# SparkFun_openScale.net
KiCad netlist of a schematic drawn in EAGLE
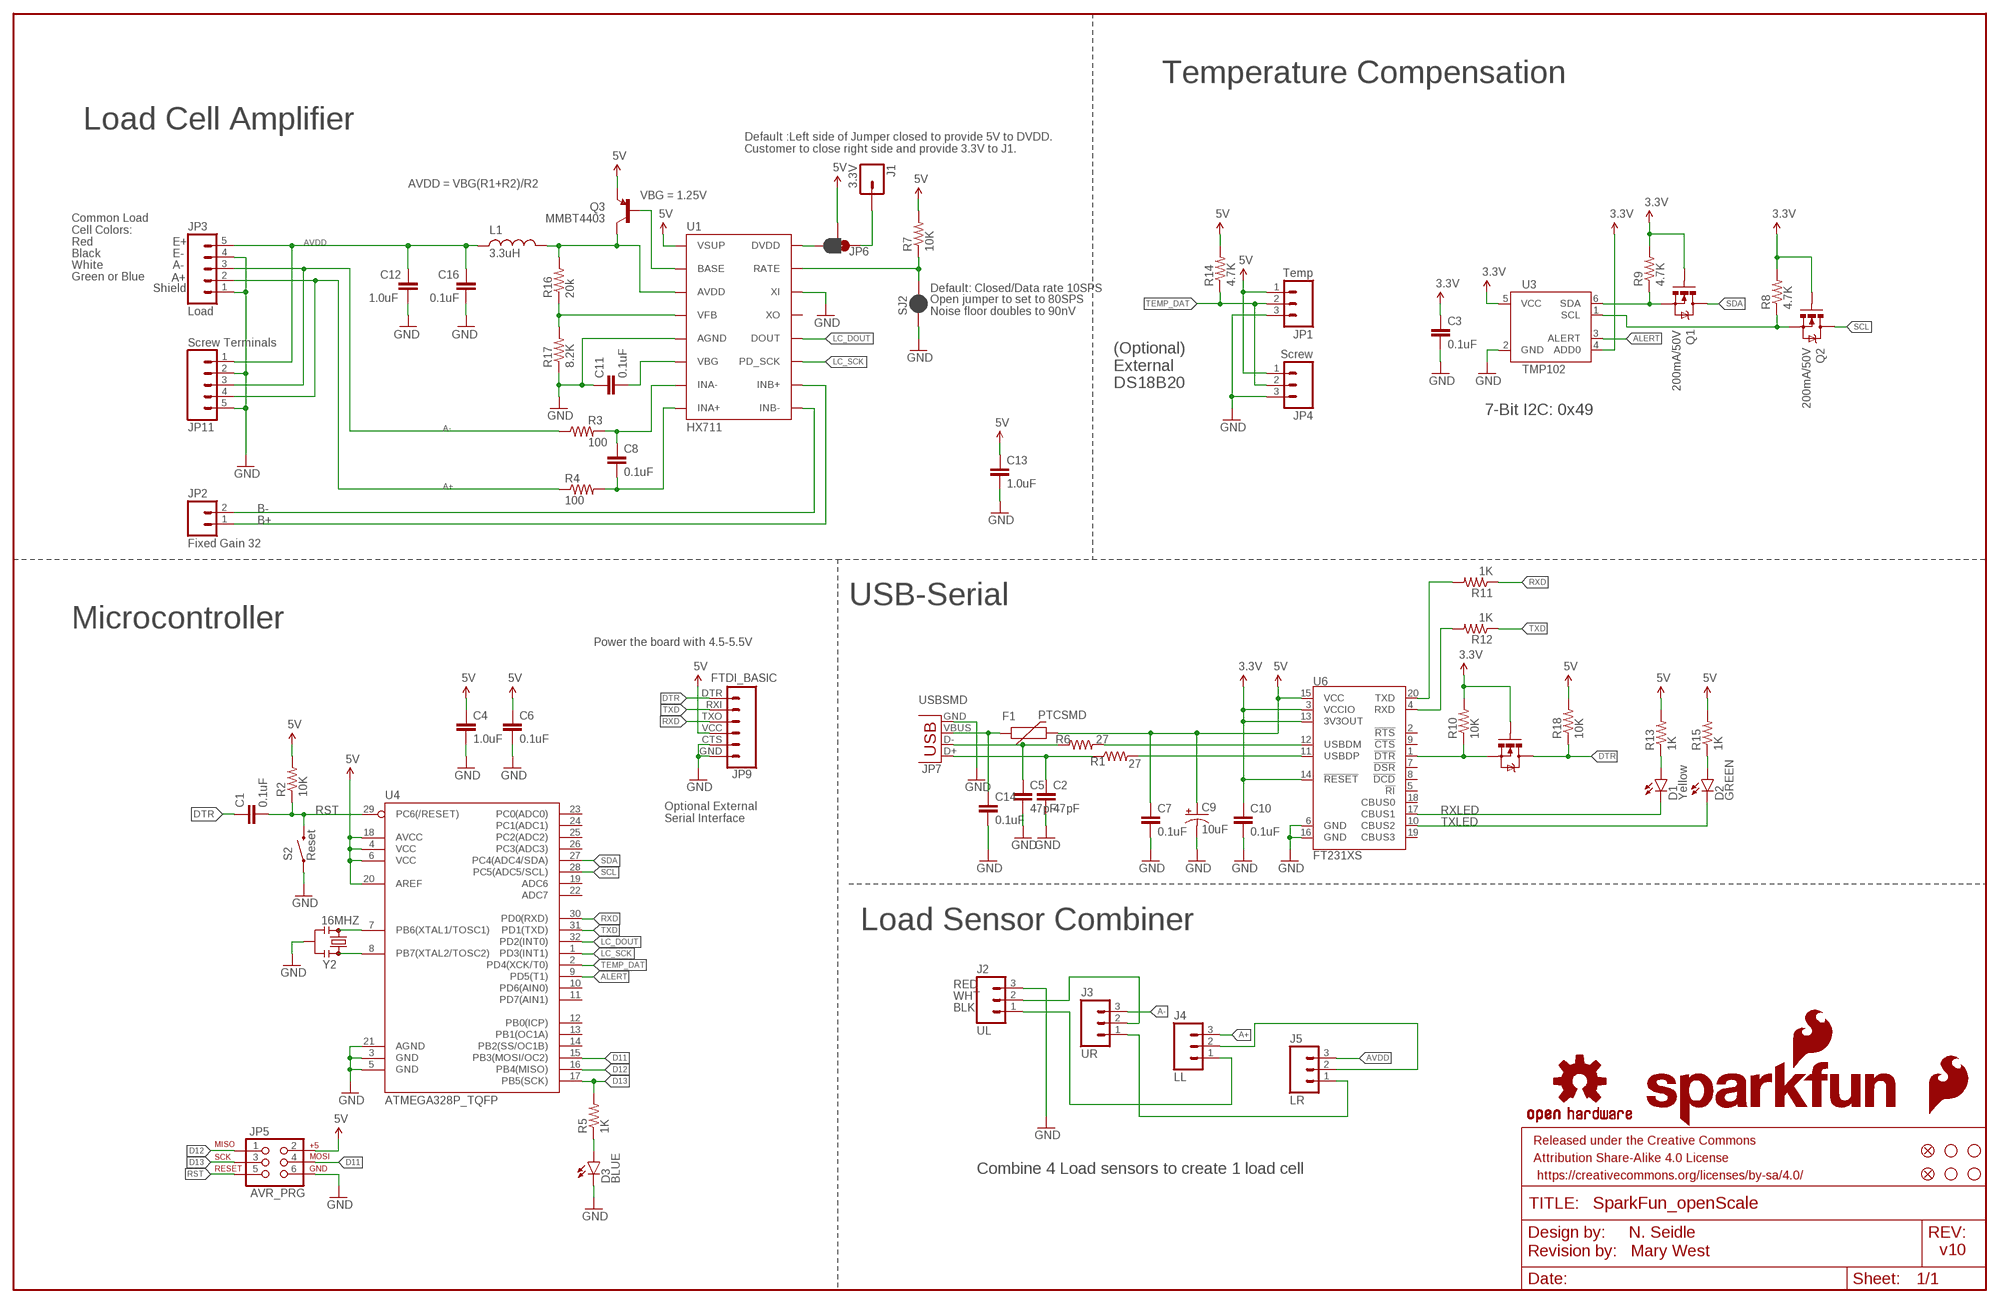
[diagram p0: schematic, sheet 1]

(export (version "E")
  (design (tool "Eeschema 10.0.6"))
  (components
    (comp (ref "C1")
      (value "0.1uF")
      (footprint "eagle-import:0603-CAP")
      (libsource (lib "eagle-import") (part "0.1UF-25V(+80/-20%)(0603)"))
    )
    (comp (ref "C2")
      (value "47pF")
      (footprint "eagle-import:0603-CAP")
      (libsource (lib "eagle-import") (part "47PF-50V-5%(0603)"))
    )
    (comp (ref "C3")
      (value "0.1uF")
      (footprint "eagle-import:0603-CAP")
      (libsource (lib "eagle-import") (part "0.1UF-25V(+80/-20%)(0603)"))
    )
    (comp (ref "C4")
      (value "1.0uF")
      (footprint "eagle-import:0603-CAP")
      (libsource (lib "eagle-import") (part "1.0UF-16V-10%(0603)"))
    )
    (comp (ref "C5")
      (value "47pF")
      (footprint "eagle-import:0603-CAP")
      (libsource (lib "eagle-import") (part "47PF-50V-5%(0603)"))
    )
    (comp (ref "C6")
      (value "0.1uF")
      (footprint "eagle-import:0603-CAP")
      (libsource (lib "eagle-import") (part "0.1UF-25V(+80/-20%)(0603)"))
    )
    (comp (ref "C7")
      (value "0.1uF")
      (footprint "eagle-import:0603-CAP")
      (libsource (lib "eagle-import") (part "0.1UF-25V(+80/-20%)(0603)"))
    )
    (comp (ref "C8")
      (value "0.1uF")
      (footprint "eagle-import:0603-CAP")
      (libsource (lib "eagle-import") (part "0.1UF-25V(+80/-20%)(0603)"))
    )
    (comp (ref "C9")
      (value "10uF")
      (footprint "eagle-import:EIA3216")
      (libsource (lib "eagle-import") (part "10UF-16V-10%(TANT)"))
    )
    (comp (ref "C10")
      (value "0.1uF")
      (footprint "eagle-import:0603-CAP")
      (libsource (lib "eagle-import") (part "0.1UF-25V(+80/-20%)(0603)"))
    )
    (comp (ref "C11")
      (value "0.1uF")
      (footprint "eagle-import:0603-CAP")
      (libsource (lib "eagle-import") (part "0.1UF-25V(+80/-20%)(0603)"))
    )
    (comp (ref "C12")
      (value "1.0uF")
      (footprint "eagle-import:0603-CAP")
      (libsource (lib "eagle-import") (part "1.0UF-16V-10%(0603)"))
    )
    (comp (ref "C13")
      (value "1.0uF")
      (footprint "eagle-import:0603-CAP")
      (libsource (lib "eagle-import") (part "1.0UF-16V-10%(0603)"))
    )
    (comp (ref "C14")
      (value "0.1uF")
      (footprint "eagle-import:0603-CAP")
      (libsource (lib "eagle-import") (part "0.1UF-25V(+80/-20%)(0603)"))
    )
    (comp (ref "C16")
      (value "0.1uF")
      (footprint "eagle-import:0603-CAP")
      (libsource (lib "eagle-import") (part "0.1UF-25V(+80/-20%)(0603)"))
    )
    (comp (ref "D1")
      (value "Yellow")
      (footprint "eagle-import:LED-1206")
      (libsource (lib "eagle-import") (part "LED-YELLOWLILYPAD"))
    )
    (comp (ref "D2")
      (value "GREEN")
      (footprint "eagle-import:LED-1206")
      (libsource (lib "eagle-import") (part "LED-GREEN1206"))
    )
    (comp (ref "D3")
      (value "BLUE")
      (footprint "eagle-import:LED-1206")
      (libsource (lib "eagle-import") (part "LED-BLUE1206"))
    )
    (comp (ref "F1")
      (value "PTCSMD")
      (footprint "eagle-import:PTC-1206")
      (libsource (lib "eagle-import") (part "PTCSMD"))
    )
    (comp (ref "FID1")
      (value "FIDUCIALUFIDUCIAL")
      (footprint "eagle-import:MICRO-FIDUCIAL")
      (libsource (lib "eagle-import") (part "FIDUCIALUFIDUCIAL"))
    )
    (comp (ref "FID2")
      (value "FIDUCIALUFIDUCIAL")
      (footprint "eagle-import:MICRO-FIDUCIAL")
      (libsource (lib "eagle-import") (part "FIDUCIALUFIDUCIAL"))
    )
    (comp (ref "FRAME1")
      (value "FRAME-LEDGER")
      (footprint "eagle-import:CREATIVE_COMMONS")
      (fields (field (name "DESIGNER") "N. Seidle") (field (name "VERSION") "v02"))
      (libsource (lib "eagle-import") (part "FRAME-LEDGER"))
    )
    (comp (ref "J1")
      (value "3.3V")
      (footprint "eagle-import:1X01")
      (libsource (lib "eagle-import") (part "M01PTH"))
    )
    (comp (ref "J2")
      (value "UL")
      (footprint "eagle-import:1X03")
      (libsource (lib "eagle-import") (part "M03PTH"))
    )
    (comp (ref "J3")
      (value "UR")
      (footprint "eagle-import:1X03")
      (libsource (lib "eagle-import") (part "M03PTH"))
    )
    (comp (ref "J4")
      (value "LL")
      (footprint "eagle-import:1X03")
      (libsource (lib "eagle-import") (part "M03PTH"))
    )
    (comp (ref "J5")
      (value "LR")
      (footprint "eagle-import:1X03")
      (libsource (lib "eagle-import") (part "M03PTH"))
    )
    (comp (ref "JP1")
      (value "Temp")
      (footprint "eagle-import:1X03_NO_SILK")
      (libsource (lib "eagle-import") (part "M031X03_NO_SILK"))
    )
    (comp (ref "JP2")
      (value "Fixed Gain 32")
      (footprint "eagle-import:1X02")
      (libsource (lib "eagle-import") (part "M02PTH"))
    )
    (comp (ref "JP3")
      (value "Load")
      (footprint "eagle-import:1X05_NO_SILK")
      (libsource (lib "eagle-import") (part "M05NO_SILK"))
    )
    (comp (ref "JP4")
      (value "Screw")
      (footprint "eagle-import:SCREWTERMINAL-3.5MM-3_LOCK.007S")
      (libsource (lib "eagle-import") (part "M03SCREW_LOCK"))
    )
    (comp (ref "JP5")
      (value "AVR_PRG")
      (footprint "eagle-import:2X3")
      (libsource (lib "eagle-import") (part "AVR_SPI_PRG_6PTH"))
    )
    (comp (ref "JP6")
      (value "JUMPER-PAD-3-2OF3_NC_BY_PASTE")
      (footprint "eagle-import:PAD-JUMPER-3-2OF3_NC_BY_PASTE_YES_SILK_FULL_BOX")
      (libsource (lib "eagle-import") (part "JUMPER-PAD-3-2OF3_NC_BY_PASTE"))
    )
    (comp (ref "JP7")
      (value "USBSMD")
      (footprint "eagle-import:USB-MINIB")
      (libsource (lib "eagle-import") (part "USBSMD"))
    )
    (comp (ref "JP9")
      (value "FTDI_BASIC")
      (footprint "eagle-import:FTDI_BASIC")
      (libsource (lib "eagle-import") (part "FTDI_BASICPTH"))
    )
    (comp (ref "JP11")
      (value "Screw Terminals")
      (footprint "eagle-import:SCREWTERMINAL-3.5MM-5")
      (libsource (lib "eagle-import") (part "M05SCREW"))
    )
    (comp (ref "L1")
      (value "3.3uH")
      (footprint "eagle-import:0805")
      (libsource (lib "eagle-import") (part "INDUCTOR0805-IND"))
    )
    (comp (ref "LOGO2")
      (value "OSHW-LOGOS")
      (footprint "eagle-import:OSHW-LOGO-S")
      (libsource (lib "eagle-import") (part "OSHW-LOGOS"))
    )
    (comp (ref "LOGO3")
      (value "SFE_LOGO_FLAME.1_INCH")
      (footprint "eagle-import:SFE_LOGO_FLAME_.1")
      (libsource (lib "eagle-import") (part "SFE_LOGO_FLAME.1_INCH"))
    )
    (comp (ref "LOGO4")
      (value "SFE_LOGO_NAME_FLAME.1_INCH")
      (footprint "eagle-import:SFE_LOGO_NAME_FLAME_.1")
      (libsource (lib "eagle-import") (part "SFE_LOGO_NAME_FLAME.1_INCH"))
    )
    (comp (ref "Q1")
      (value "200mA/50V")
      (footprint "eagle-import:SOT23-3")
      (libsource (lib "eagle-import") (part "MOSFET-NCHANNELBSS138"))
    )
    (comp (ref "Q2")
      (value "200mA/50V")
      (footprint "eagle-import:SOT23-3")
      (libsource (lib "eagle-import") (part "MOSFET-NCHANNELBSS138"))
    )
    (comp (ref "Q3")
      (value "MMBT4403")
      (footprint "eagle-import:SOT23-3")
      (libsource (lib "eagle-import") (part "TRANSISTOR_PNPMMBT4403"))
    )
    (comp (ref "Q4")
      (value "MOSFET-NCHANNEL2N7002PW")
      (footprint "eagle-import:SOT323")
      (libsource (lib "eagle-import") (part "MOSFET-NCHANNEL2N7002PW"))
    )
    (comp (ref "R1")
      (value "27")
      (footprint "eagle-import:0603")
      (libsource (lib "eagle-import") (part "27OHM1/10W1%(0603)"))
    )
    (comp (ref "R2")
      (value "10K")
      (footprint "eagle-import:0603-RES")
      (libsource (lib "eagle-import") (part "10KOHM-1/10W-1%(0603)0603"))
    )
    (comp (ref "R3")
      (value "100")
      (footprint "eagle-import:0603-RES")
      (libsource (lib "eagle-import") (part "100OHM-1/10W-1%(0603)"))
    )
    (comp (ref "R4")
      (value "100")
      (footprint "eagle-import:0603-RES")
      (libsource (lib "eagle-import") (part "100OHM-1/10W-1%(0603)"))
    )
    (comp (ref "R5")
      (value "1K")
      (footprint "eagle-import:0603-RES")
      (libsource (lib "eagle-import") (part "1KOHM-1/10W-1%(0603)"))
    )
    (comp (ref "R6")
      (value "27")
      (footprint "eagle-import:0603")
      (libsource (lib "eagle-import") (part "27OHM1/10W1%(0603)"))
    )
    (comp (ref "R7")
      (value "10K")
      (footprint "eagle-import:0603-RES")
      (libsource (lib "eagle-import") (part "10KOHM-1/10W-1%(0603)0603"))
    )
    (comp (ref "R8")
      (value "4.7K")
      (footprint "eagle-import:0603-RES")
      (libsource (lib "eagle-import") (part "4.7KOHM-1/10W-1%(0603)"))
    )
    (comp (ref "R9")
      (value "4.7K")
      (footprint "eagle-import:0603-RES")
      (libsource (lib "eagle-import") (part "4.7KOHM-1/10W-1%(0603)"))
    )
    (comp (ref "R10")
      (value "10K")
      (footprint "eagle-import:0603-RES")
      (libsource (lib "eagle-import") (part "10KOHM-1/10W-1%(0603)0603"))
    )
    (comp (ref "R11")
      (value "1K")
      (footprint "eagle-import:0603-RES")
      (libsource (lib "eagle-import") (part "1KOHM-1/10W-1%(0603)"))
    )
    (comp (ref "R12")
      (value "1K")
      (footprint "eagle-import:0603-RES")
      (libsource (lib "eagle-import") (part "1KOHM-1/10W-1%(0603)"))
    )
    (comp (ref "R13")
      (value "1K")
      (footprint "eagle-import:0603-RES")
      (libsource (lib "eagle-import") (part "1KOHM-1/10W-1%(0603)"))
    )
    (comp (ref "R14")
      (value "4.7K")
      (footprint "eagle-import:0603-RES")
      (libsource (lib "eagle-import") (part "4.7KOHM-1/10W-1%(0603)"))
    )
    (comp (ref "R15")
      (value "1K")
      (footprint "eagle-import:0603-RES")
      (libsource (lib "eagle-import") (part "1KOHM-1/10W-1%(0603)"))
    )
    (comp (ref "R16")
      (value "20k")
      (footprint "eagle-import:0603-RES")
      (libsource (lib "eagle-import") (part "20KOHM1/10W1%(0603)"))
    )
    (comp (ref "R17")
      (value "8.2K")
      (footprint "eagle-import:0603-RES")
      (libsource (lib "eagle-import") (part "8.2KOHM-1/10W-5%(0603)"))
    )
    (comp (ref "R18")
      (value "10K")
      (footprint "eagle-import:0603-RES")
      (libsource (lib "eagle-import") (part "10KOHM-1/10W-1%(0603)0603"))
    )
    (comp (ref "S2")
      (value "Reset")
      (footprint "eagle-import:TACTILE-SWITCH-SMD")
      (libsource (lib "eagle-import") (part "SWITCH-MOMENTARY-2SMD"))
    )
    (comp (ref "SJ2")
      (value "JUMPER-PAD-2-NC_BY_PASTE")
      (footprint "eagle-import:PAD-JUMPER-2-NC_BY_PASTE_YES_SILK")
      (libsource (lib "eagle-import") (part "JUMPER-PAD-2-NC_BY_PASTE"))
    )
    (comp (ref "STANDOFF1")
      (value "STAND-OFF")
      (footprint "eagle-import:STAND-OFF")
      (libsource (lib "eagle-import") (part "STAND-OFF"))
    )
    (comp (ref "STANDOFF2")
      (value "STAND-OFF")
      (footprint "eagle-import:STAND-OFF")
      (libsource (lib "eagle-import") (part "STAND-OFF"))
    )
    (comp (ref "STANDOFF3")
      (value "STAND-OFF")
      (footprint "eagle-import:STAND-OFF")
      (libsource (lib "eagle-import") (part "STAND-OFF"))
    )
    (comp (ref "STANDOFF4")
      (value "STAND-OFF")
      (footprint "eagle-import:STAND-OFF")
      (libsource (lib "eagle-import") (part "STAND-OFF"))
    )
    (comp (ref "U1")
      (value "HX711")
      (footprint "eagle-import:SO16")
      (libsource (lib "eagle-import") (part "HX711HX711"))
    )
    (comp (ref "U3")
      (value "TMP102")
      (footprint "eagle-import:SOT563")
      (libsource (lib "eagle-import") (part "TMP102"))
    )
    (comp (ref "U4")
      (value "ATMEGA328P_TQFP")
      (footprint "eagle-import:TQFP32-08")
      (libsource (lib "eagle-import") (part "ATMEGA328P_TQFP"))
    )
    (comp (ref "U6")
      (value "FT231XS")
      (footprint "eagle-import:SSOP20_L")
      (libsource (lib "eagle-import") (part "FT231XS"))
    )
    (comp (ref "Y2")
      (value "16MHZ")
      (footprint "eagle-import:RESONATOR-SMD")
      (libsource (lib "eagle-import") (part "RESONATOR16MHZ"))
    )
  )
  (nets
    (net (code "1") (name "/B+") (class "Default")
      (node (ref "JP2") (pin "1") (pinfunction "1_1") (pintype "passive"))
      (node (ref "U1") (pin "10") (pinfunction "INB+_10") (pintype "bidirectional"))
    )
    (net (code "2") (name "/B-") (class "Default")
      (node (ref "JP2") (pin "2") (pinfunction "2_2") (pintype "passive"))
      (node (ref "U1") (pin "9") (pinfunction "INB-_9") (pintype "bidirectional"))
    )
    (net (code "3") (name "/RXLED") (class "Default")
      (node (ref "D1") (pin "C") (pinfunction "C_C") (pintype "passive"))
      (node (ref "U6") (pin "17") (pinfunction "CBUS1_17") (pintype "bidirectional"))
    )
    (net (code "4") (name "/TXLED") (class "Default")
      (node (ref "D2") (pin "C") (pinfunction "C_C") (pintype "passive"))
      (node (ref "U6") (pin "10") (pinfunction "CBUS2_10") (pintype "bidirectional"))
    )
    (net (code "5") (name "3.3V") (class "Default")
      (node (ref "C10") (pin "1") (pinfunction "1_1") (pintype "passive"))
      (node (ref "C3") (pin "1") (pinfunction "1_1") (pintype "passive"))
      (node (ref "Q1") (pin "1") (pinfunction "G_1") (pintype "passive"))
      (node (ref "Q2") (pin "1") (pinfunction "G_1") (pintype "passive"))
      (node (ref "Q4") (pin "1") (pinfunction "G_1") (pintype "passive"))
      (node (ref "R10") (pin "2") (pinfunction "2_2") (pintype "passive"))
      (node (ref "R8") (pin "2") (pinfunction "2_2") (pintype "passive"))
      (node (ref "R9") (pin "2") (pinfunction "2_2") (pintype "passive"))
      (node (ref "U3") (pin "4") (pinfunction "ADD0_4") (pintype "bidirectional"))
      (node (ref "U3") (pin "5") (pinfunction "VCC_5") (pintype "bidirectional"))
      (node (ref "U6") (pin "13") (pinfunction "3V3OUT_13") (pintype "bidirectional"))
      (node (ref "U6") (pin "14") (pinfunction "~{RESET}_14") (pintype "bidirectional"))
      (node (ref "U6") (pin "3") (pinfunction "VCCIO_3") (pintype "bidirectional"))
    )
    (net (code "6") (name "5V") (class "Default")
      (node (ref "C13") (pin "1") (pinfunction "1_1") (pintype "passive"))
      (node (ref "C4") (pin "1") (pinfunction "1_1") (pintype "passive"))
      (node (ref "C6") (pin "1") (pinfunction "1_1") (pintype "passive"))
      (node (ref "C7") (pin "1") (pinfunction "1_1") (pintype "passive"))
      (node (ref "C9") (pin "A") (pinfunction "+_A") (pintype "passive"))
      (node (ref "F1") (pin "2") (pinfunction "2_2") (pintype "bidirectional"))
      (node (ref "JP1") (pin "1") (pinfunction "1_1") (pintype "passive"))
      (node (ref "JP4") (pin "1") (pinfunction "1_1") (pintype "passive"))
      (node (ref "JP5") (pin "2") (pinfunction "2_2") (pintype "passive"))
      (node (ref "JP6") (pin "2") (pinfunction "2_2") (pintype "passive"))
      (node (ref "JP9") (pin "VCC") (pinfunction "4_VCC") (pintype "passive"))
      (node (ref "Q3") (pin "2") (pinfunction "E_2") (pintype "passive"))
      (node (ref "R13") (pin "2") (pinfunction "2_2") (pintype "passive"))
      (node (ref "R14") (pin "2") (pinfunction "2_2") (pintype "passive"))
      (node (ref "R15") (pin "2") (pinfunction "2_2") (pintype "passive"))
      (node (ref "R18") (pin "2") (pinfunction "2_2") (pintype "passive"))
      (node (ref "R2") (pin "2") (pinfunction "2_2") (pintype "passive"))
      (node (ref "R7") (pin "2") (pinfunction "2_2") (pintype "passive"))
      (node (ref "U1") (pin "1") (pinfunction "VSUP_1") (pintype "bidirectional"))
      (node (ref "U4") (pin "18") (pinfunction "AVCC_18") (pintype "bidirectional"))
      (node (ref "U4") (pin "20") (pinfunction "AREF_20") (pintype "bidirectional"))
      (node (ref "U4") (pin "4") (pinfunction "VCC_4") (pintype "bidirectional"))
      (node (ref "U4") (pin "6") (pinfunction "VCC_6") (pintype "bidirectional"))
      (node (ref "U6") (pin "15") (pinfunction "VCC_15") (pintype "bidirectional"))
    )
    (net (code "7") (name "A+") (class "Default")
      (node (ref "J4") (pin "3") (pinfunction "3_3") (pintype "passive"))
      (node (ref "JP11") (pin "4") (pinfunction "4_4") (pintype "passive"))
      (node (ref "JP3") (pin "2") (pinfunction "2_2") (pintype "passive"))
      (node (ref "R4") (pin "1") (pinfunction "1_1") (pintype "passive"))
    )
    (net (code "8") (name "A-") (class "Default")
      (node (ref "J3") (pin "3") (pinfunction "3_3") (pintype "passive"))
      (node (ref "JP11") (pin "3") (pinfunction "3_3") (pintype "passive"))
      (node (ref "JP3") (pin "3") (pinfunction "3_3") (pintype "passive"))
      (node (ref "R3") (pin "1") (pinfunction "1_1") (pintype "passive"))
    )
    (net (code "9") (name "ALERT") (class "Default")
      (node (ref "U3") (pin "3") (pinfunction "ALERT_3") (pintype "bidirectional"))
      (node (ref "U4") (pin "9") (pinfunction "PD5(T1)_9") (pintype "bidirectional"))
    )
    (net (code "10") (name "AVDD") (class "Default")
      (node (ref "C12") (pin "2") (pinfunction "2_2") (pintype "passive"))
      (node (ref "C16") (pin "1") (pinfunction "1_1") (pintype "passive"))
      (node (ref "J5") (pin "3") (pinfunction "3_3") (pintype "passive"))
      (node (ref "JP11") (pin "1") (pinfunction "1_1") (pintype "passive"))
      (node (ref "JP3") (pin "5") (pinfunction "5_5") (pintype "passive"))
      (node (ref "L1") (pin "1") (pinfunction "1_1") (pintype "passive"))
    )
    (net (code "11") (name "D11") (class "Default")
      (node (ref "JP5") (pin "4") (pinfunction "4_4") (pintype "passive"))
      (node (ref "U4") (pin "15") (pinfunction "PB3(MOSI/OC2)_15") (pintype "bidirectional"))
    )
    (net (code "12") (name "D12") (class "Default")
      (node (ref "JP5") (pin "1") (pinfunction "1_1") (pintype "passive"))
      (node (ref "U4") (pin "16") (pinfunction "PB4(MISO)_16") (pintype "bidirectional"))
    )
    (net (code "13") (name "D13") (class "Default")
      (node (ref "JP5") (pin "3") (pinfunction "3_3") (pintype "passive"))
      (node (ref "R5") (pin "2") (pinfunction "2_2") (pintype "passive"))
      (node (ref "U4") (pin "17") (pinfunction "PB5(SCK)_17") (pintype "bidirectional"))
    )
    (net (code "14") (name "DTR") (class "Default")
      (node (ref "C1") (pin "1") (pinfunction "1_1") (pintype "passive"))
      (node (ref "JP9") (pin "DTR") (pinfunction "1_DTR") (pintype "passive"))
      (node (ref "Q4") (pin "3") (pinfunction "D_3") (pintype "passive"))
      (node (ref "R18") (pin "1") (pinfunction "1_1") (pintype "passive"))
    )
    (net (code "15") (name "GND") (class "Default")
      (node (ref "C10") (pin "2") (pinfunction "2_2") (pintype "passive"))
      (node (ref "C11") (pin "1") (pinfunction "1_1") (pintype "passive"))
      (node (ref "C12") (pin "1") (pinfunction "1_1") (pintype "passive"))
      (node (ref "C13") (pin "2") (pinfunction "2_2") (pintype "passive"))
      (node (ref "C14") (pin "2") (pinfunction "2_2") (pintype "passive"))
      (node (ref "C16") (pin "2") (pinfunction "2_2") (pintype "passive"))
      (node (ref "C2") (pin "2") (pinfunction "2_2") (pintype "passive"))
      (node (ref "C3") (pin "2") (pinfunction "2_2") (pintype "passive"))
      (node (ref "C4") (pin "2") (pinfunction "2_2") (pintype "passive"))
      (node (ref "C5") (pin "2") (pinfunction "2_2") (pintype "passive"))
      (node (ref "C6") (pin "2") (pinfunction "2_2") (pintype "passive"))
      (node (ref "C7") (pin "2") (pinfunction "2_2") (pintype "passive"))
      (node (ref "C9") (pin "C") (pinfunction "-_C") (pintype "passive"))
      (node (ref "D3") (pin "C") (pinfunction "C_C") (pintype "passive"))
      (node (ref "J2") (pin "3") (pinfunction "3_3") (pintype "passive"))
      (node (ref "JP1") (pin "3") (pinfunction "3_3") (pintype "passive"))
      (node (ref "JP11") (pin "2") (pinfunction "2_2") (pintype "passive"))
      (node (ref "JP11") (pin "5") (pinfunction "5_5") (pintype "passive"))
      (node (ref "JP3") (pin "1") (pinfunction "1_1") (pintype "passive"))
      (node (ref "JP3") (pin "4") (pinfunction "4_4") (pintype "passive"))
      (node (ref "JP4") (pin "3") (pinfunction "3_3") (pintype "passive"))
      (node (ref "JP5") (pin "6") (pinfunction "6_6") (pintype "passive"))
      (node (ref "JP7") (pin "GND") (pinfunction "GND_GND") (pintype "bidirectional"))
      (node (ref "JP9") (pin "CTS") (pinfunction "5_CTS") (pintype "passive"))
      (node (ref "JP9") (pin "GND") (pinfunction "6_GND") (pintype "passive"))
      (node (ref "R17") (pin "1") (pinfunction "1_1") (pintype "passive"))
      (node (ref "S2") (pin "1") (pinfunction "1_1") (pintype "passive"))
      (node (ref "SJ2") (pin "1") (pinfunction "1_1") (pintype "passive"))
      (node (ref "U1") (pin "14") (pinfunction "XI_14") (pintype "bidirectional"))
      (node (ref "U1") (pin "5") (pinfunction "AGND_5") (pintype "bidirectional"))
      (node (ref "U3") (pin "2") (pinfunction "GND_2") (pintype "bidirectional"))
      (node (ref "U4") (pin "21") (pinfunction "AGND_21") (pintype "bidirectional"))
      (node (ref "U4") (pin "3") (pinfunction "GND_3") (pintype "bidirectional"))
      (node (ref "U4") (pin "5") (pinfunction "GND_5") (pintype "bidirectional"))
      (node (ref "U6") (pin "16") (pinfunction "GND_16") (pintype "bidirectional"))
      (node (ref "U6") (pin "6") (pinfunction "GND_6") (pintype "bidirectional"))
      (node (ref "Y2") (pin "2") (pinfunction "2_2") (pintype "passive"))
    )
    (net (code "16") (name "LC_DOUT") (class "Default")
      (node (ref "U1") (pin "12") (pinfunction "DOUT_12") (pintype "bidirectional"))
      (node (ref "U4") (pin "32") (pinfunction "PD2(INT0)_32") (pintype "bidirectional"))
    )
    (net (code "17") (name "LC_SCK") (class "Default")
      (node (ref "U1") (pin "11") (pinfunction "PD_SCK_11") (pintype "bidirectional"))
      (node (ref "U4") (pin "1") (pinfunction "PD3(INT1)_1") (pintype "bidirectional"))
    )
    (net (code "18") (name "Net-(C2-Pad1)") (class "Default")
      (node (ref "C2") (pin "1") (pinfunction "1_1") (pintype "passive"))
      (node (ref "JP7") (pin "D+") (pinfunction "D+_D+") (pintype "bidirectional"))
      (node (ref "R1") (pin "1") (pinfunction "1_1") (pintype "passive"))
    )
    (net (code "19") (name "Net-(C5-Pad1)") (class "Default")
      (node (ref "C5") (pin "1") (pinfunction "1_1") (pintype "passive"))
      (node (ref "JP7") (pin "D-") (pinfunction "D-_D-") (pintype "bidirectional"))
      (node (ref "R6") (pin "1") (pinfunction "1_1") (pintype "passive"))
    )
    (net (code "20") (name "Net-(C14-Pad1)") (class "Default")
      (node (ref "C14") (pin "1") (pinfunction "1_1") (pintype "passive"))
      (node (ref "F1") (pin "1") (pinfunction "1_1") (pintype "bidirectional"))
      (node (ref "JP7") (pin "VBUS") (pinfunction "VBUS_VBUS") (pintype "bidirectional"))
    )
    (net (code "21") (name "Net-(D1-PadA)") (class "Default")
      (node (ref "D1") (pin "A") (pinfunction "A_A") (pintype "passive"))
      (node (ref "R13") (pin "1") (pinfunction "1_1") (pintype "passive"))
    )
    (net (code "22") (name "Net-(D2-PadA)") (class "Default")
      (node (ref "D2") (pin "A") (pinfunction "A_A") (pintype "passive"))
      (node (ref "R15") (pin "1") (pinfunction "1_1") (pintype "passive"))
    )
    (net (code "23") (name "Net-(D3-PadA)") (class "Default")
      (node (ref "D3") (pin "A") (pinfunction "A_A") (pintype "passive"))
      (node (ref "R5") (pin "1") (pinfunction "1_1") (pintype "passive"))
    )
    (net (code "24") (name "Net-(J1-Pad1)") (class "Default")
      (node (ref "J1") (pin "1") (pinfunction "1_1") (pintype "passive"))
      (node (ref "JP6") (pin "1") (pinfunction "1_1") (pintype "passive"))
    )
    (net (code "25") (name "Net-(J2-Pad1)") (class "Default")
      (node (ref "J2") (pin "1") (pinfunction "1_1") (pintype "passive"))
      (node (ref "J4") (pin "1") (pinfunction "1_1") (pintype "passive"))
    )
    (net (code "26") (name "Net-(J2-Pad2)") (class "Default")
      (node (ref "J2") (pin "2") (pinfunction "2_2") (pintype "passive"))
      (node (ref "J3") (pin "2") (pinfunction "2_2") (pintype "passive"))
    )
    (net (code "27") (name "Net-(J3-Pad1)") (class "Default")
      (node (ref "J3") (pin "1") (pinfunction "1_1") (pintype "passive"))
      (node (ref "J5") (pin "1") (pinfunction "1_1") (pintype "passive"))
    )
    (net (code "28") (name "Net-(J4-Pad2)") (class "Default")
      (node (ref "J4") (pin "2") (pinfunction "2_2") (pintype "passive"))
      (node (ref "J5") (pin "2") (pinfunction "2_2") (pintype "passive"))
    )
    (net (code "29") (name "Net-(Q1-S)") (class "Default")
      (node (ref "Q1") (pin "2") (pinfunction "S_2") (pintype "passive"))
      (node (ref "R9") (pin "1") (pinfunction "1_1") (pintype "passive"))
      (node (ref "U3") (pin "6") (pinfunction "SDA_6") (pintype "bidirectional"))
    )
    (net (code "30") (name "Net-(Q2-S)") (class "Default")
      (node (ref "Q2") (pin "2") (pinfunction "S_2") (pintype "passive"))
      (node (ref "R8") (pin "1") (pinfunction "1_1") (pintype "passive"))
      (node (ref "U3") (pin "1") (pinfunction "SCL_1") (pintype "bidirectional"))
    )
    (net (code "31") (name "Net-(Q3-B)") (class "Default")
      (node (ref "Q3") (pin "1") (pinfunction "B_1") (pintype "passive"))
      (node (ref "U1") (pin "2") (pinfunction "BASE_2") (pintype "bidirectional"))
    )
    (net (code "32") (name "Net-(Q3-C)") (class "Default")
      (node (ref "L1") (pin "2") (pinfunction "2_2") (pintype "passive"))
      (node (ref "Q3") (pin "3") (pinfunction "C_3") (pintype "passive"))
      (node (ref "R16") (pin "2") (pinfunction "2_2") (pintype "passive"))
      (node (ref "U1") (pin "3") (pinfunction "AVDD_3") (pintype "bidirectional"))
    )
    (net (code "33") (name "Net-(Q4-S)") (class "Default")
      (node (ref "Q4") (pin "2") (pinfunction "S_2") (pintype "passive"))
      (node (ref "R10") (pin "1") (pinfunction "1_1") (pintype "passive"))
      (node (ref "U6") (pin "1") (pinfunction "~{DTR}_1") (pintype "bidirectional"))
    )
    (net (code "34") (name "Net-(U1-DVDD)") (class "Default")
      (node (ref "JP6") (pin "3") (pinfunction "3_3") (pintype "passive"))
      (node (ref "U1") (pin "16") (pinfunction "DVDD_16") (pintype "bidirectional"))
    )
    (net (code "35") (name "Net-(U1-INA+)") (class "Default")
      (node (ref "C8") (pin "2") (pinfunction "2_2") (pintype "passive"))
      (node (ref "R4") (pin "2") (pinfunction "2_2") (pintype "passive"))
      (node (ref "U1") (pin "8") (pinfunction "INA+_8") (pintype "bidirectional"))
    )
    (net (code "36") (name "Net-(U1-INA-)") (class "Default")
      (node (ref "C8") (pin "1") (pinfunction "1_1") (pintype "passive"))
      (node (ref "R3") (pin "2") (pinfunction "2_2") (pintype "passive"))
      (node (ref "U1") (pin "7") (pinfunction "INA-_7") (pintype "bidirectional"))
    )
    (net (code "37") (name "Net-(U1-RATE)") (class "Default")
      (node (ref "R7") (pin "1") (pinfunction "1_1") (pintype "passive"))
      (node (ref "SJ2") (pin "2") (pinfunction "2_2") (pintype "passive"))
      (node (ref "U1") (pin "15") (pinfunction "RATE_15") (pintype "bidirectional"))
    )
    (net (code "38") (name "Net-(U1-VBG)") (class "Default")
      (node (ref "C11") (pin "2") (pinfunction "2_2") (pintype "passive"))
      (node (ref "U1") (pin "6") (pinfunction "VBG_6") (pintype "bidirectional"))
    )
    (net (code "39") (name "Net-(U1-VFB)") (class "Default")
      (node (ref "R16") (pin "1") (pinfunction "1_1") (pintype "passive"))
      (node (ref "R17") (pin "2") (pinfunction "2_2") (pintype "passive"))
      (node (ref "U1") (pin "4") (pinfunction "VFB_4") (pintype "bidirectional"))
    )
    (net (code "40") (name "Net-(U4-PB6(XTAL1{slash}TOSC1))") (class "Default")
      (node (ref "U4") (pin "7") (pinfunction "PB6(XTAL1/TOSC1)_7") (pintype "bidirectional"))
      (node (ref "Y2") (pin "1") (pinfunction "1_1") (pintype "passive"))
    )
    (net (code "41") (name "Net-(U4-PB7(XTAL2{slash}TOSC2))") (class "Default")
      (node (ref "U4") (pin "8") (pinfunction "PB7(XTAL2/TOSC2)_8") (pintype "bidirectional"))
      (node (ref "Y2") (pin "3") (pinfunction "3_3") (pintype "passive"))
    )
    (net (code "42") (name "Net-(U6-RXD)") (class "Default")
      (node (ref "R12") (pin "2") (pinfunction "2_2") (pintype "passive"))
      (node (ref "U6") (pin "4") (pinfunction "RXD_4") (pintype "bidirectional"))
    )
    (net (code "43") (name "Net-(U6-TXD)") (class "Default")
      (node (ref "R11") (pin "2") (pinfunction "2_2") (pintype "passive"))
      (node (ref "U6") (pin "20") (pinfunction "TXD_20") (pintype "bidirectional"))
    )
    (net (code "44") (name "Net-(U6-USBDM)") (class "Default")
      (node (ref "R6") (pin "2") (pinfunction "2_2") (pintype "passive"))
      (node (ref "U6") (pin "12") (pinfunction "USBDM_12") (pintype "bidirectional"))
    )
    (net (code "45") (name "Net-(U6-USBDP)") (class "Default")
      (node (ref "R1") (pin "2") (pinfunction "2_2") (pintype "passive"))
      (node (ref "U6") (pin "11") (pinfunction "USBDP_11") (pintype "bidirectional"))
    )
    (net (code "46") (name "RST") (class "Default")
      (node (ref "C1") (pin "2") (pinfunction "2_2") (pintype "passive"))
      (node (ref "JP5") (pin "5") (pinfunction "5_5") (pintype "passive"))
      (node (ref "R2") (pin "1") (pinfunction "1_1") (pintype "passive"))
      (node (ref "S2") (pin "3") (pinfunction "2_3") (pintype "passive"))
      (node (ref "U4") (pin "29") (pinfunction "PC6(/RESET)_29") (pintype "bidirectional"))
    )
    (net (code "47") (name "RXD") (class "Default")
      (node (ref "JP9") (pin "TXO") (pinfunction "3_TXO") (pintype "passive"))
      (node (ref "R11") (pin "1") (pinfunction "1_1") (pintype "passive"))
      (node (ref "U4") (pin "30") (pinfunction "PD0(RXD)_30") (pintype "bidirectional"))
    )
    (net (code "48") (name "SCL") (class "Default")
      (node (ref "Q2") (pin "3") (pinfunction "D_3") (pintype "passive"))
      (node (ref "U4") (pin "28") (pinfunction "PC5(ADC5/SCL)_28") (pintype "bidirectional"))
    )
    (net (code "49") (name "SDA") (class "Default")
      (node (ref "Q1") (pin "3") (pinfunction "D_3") (pintype "passive"))
      (node (ref "U4") (pin "27") (pinfunction "PC4(ADC4/SDA)_27") (pintype "bidirectional"))
    )
    (net (code "50") (name "TEMP_DAT") (class "Default")
      (node (ref "JP1") (pin "2") (pinfunction "2_2") (pintype "passive"))
      (node (ref "JP4") (pin "2") (pinfunction "2_2") (pintype "passive"))
      (node (ref "R14") (pin "1") (pinfunction "1_1") (pintype "passive"))
      (node (ref "U4") (pin "2") (pinfunction "PD4(XCK/T0)_2") (pintype "bidirectional"))
    )
    (net (code "51") (name "TXD") (class "Default")
      (node (ref "JP9") (pin "RXI") (pinfunction "2_RXI") (pintype "passive"))
      (node (ref "R12") (pin "1") (pinfunction "1_1") (pintype "passive"))
      (node (ref "U4") (pin "31") (pinfunction "PD1(TXD)_31") (pintype "bidirectional"))
    )
    (net (code "52") (name "unconnected-(U1-XO-Pad13)") (class "Default")
      (node (ref "U1") (pin "13") (pinfunction "XO_13") (pintype "bidirectional"))
    )
    (net (code "53") (name "unconnected-(U4-ADC6-Pad19)") (class "Default")
      (node (ref "U4") (pin "19") (pinfunction "ADC6_19") (pintype "bidirectional"))
    )
    (net (code "54") (name "unconnected-(U4-ADC7-Pad22)") (class "Default")
      (node (ref "U4") (pin "22") (pinfunction "ADC7_22") (pintype "bidirectional"))
    )
    (net (code "55") (name "unconnected-(U4-PB0(ICP)-Pad12)") (class "Default")
      (node (ref "U4") (pin "12") (pinfunction "PB0(ICP)_12") (pintype "bidirectional"))
    )
    (net (code "56") (name "unconnected-(U4-PB1(OC1A)-Pad13)") (class "Default")
      (node (ref "U4") (pin "13") (pinfunction "PB1(OC1A)_13") (pintype "bidirectional"))
    )
    (net (code "57") (name "unconnected-(U4-PB2(SS{slash}OC1B)-Pad14)") (class "Default")
      (node (ref "U4") (pin "14") (pinfunction "PB2(SS/OC1B)_14") (pintype "bidirectional"))
    )
    (net (code "58") (name "unconnected-(U4-PC0(ADC0)-Pad23)") (class "Default")
      (node (ref "U4") (pin "23") (pinfunction "PC0(ADC0)_23") (pintype "bidirectional"))
    )
    (net (code "59") (name "unconnected-(U4-PC1(ADC1)-Pad24)") (class "Default")
      (node (ref "U4") (pin "24") (pinfunction "PC1(ADC1)_24") (pintype "bidirectional"))
    )
    (net (code "60") (name "unconnected-(U4-PC2(ADC2)-Pad25)") (class "Default")
      (node (ref "U4") (pin "25") (pinfunction "PC2(ADC2)_25") (pintype "bidirectional"))
    )
    (net (code "61") (name "unconnected-(U4-PC3(ADC3)-Pad26)") (class "Default")
      (node (ref "U4") (pin "26") (pinfunction "PC3(ADC3)_26") (pintype "bidirectional"))
    )
    (net (code "62") (name "unconnected-(U4-PD6(AIN0)-Pad10)") (class "Default")
      (node (ref "U4") (pin "10") (pinfunction "PD6(AIN0)_10") (pintype "bidirectional"))
    )
    (net (code "63") (name "unconnected-(U4-PD7(AIN1)-Pad11)") (class "Default")
      (node (ref "U4") (pin "11") (pinfunction "PD7(AIN1)_11") (pintype "bidirectional"))
    )
    (net (code "64") (name "unconnected-(U6-CBUS0-Pad18)") (class "Default")
      (node (ref "U6") (pin "18") (pinfunction "CBUS0_18") (pintype "bidirectional"))
    )
    (net (code "65") (name "unconnected-(U6-CBUS3-Pad19)") (class "Default")
      (node (ref "U6") (pin "19") (pinfunction "CBUS3_19") (pintype "bidirectional"))
    )
    (net (code "66") (name "unconnected-(U6-~{CTS}-Pad9)") (class "Default")
      (node (ref "U6") (pin "9") (pinfunction "~{CTS}_9") (pintype "bidirectional"))
    )
    (net (code "67") (name "unconnected-(U6-~{DCD}-Pad8)") (class "Default")
      (node (ref "U6") (pin "8") (pinfunction "~{DCD}_8") (pintype "bidirectional"))
    )
    (net (code "68") (name "unconnected-(U6-~{DSR}-Pad7)") (class "Default")
      (node (ref "U6") (pin "7") (pinfunction "~{DSR}_7") (pintype "bidirectional"))
    )
    (net (code "69") (name "unconnected-(U6-~{RI}-Pad5)") (class "Default")
      (node (ref "U6") (pin "5") (pinfunction "~{RI}_5") (pintype "bidirectional"))
    )
    (net (code "70") (name "unconnected-(U6-~{RTS}-Pad2)") (class "Default")
      (node (ref "U6") (pin "2") (pinfunction "~{RTS}_2") (pintype "bidirectional"))
    )
  )
)
